# 491_Circuit_Schematic_to_MILL_mixed_4th.net
KiCad netlist of a schematic drawn in EAGLE
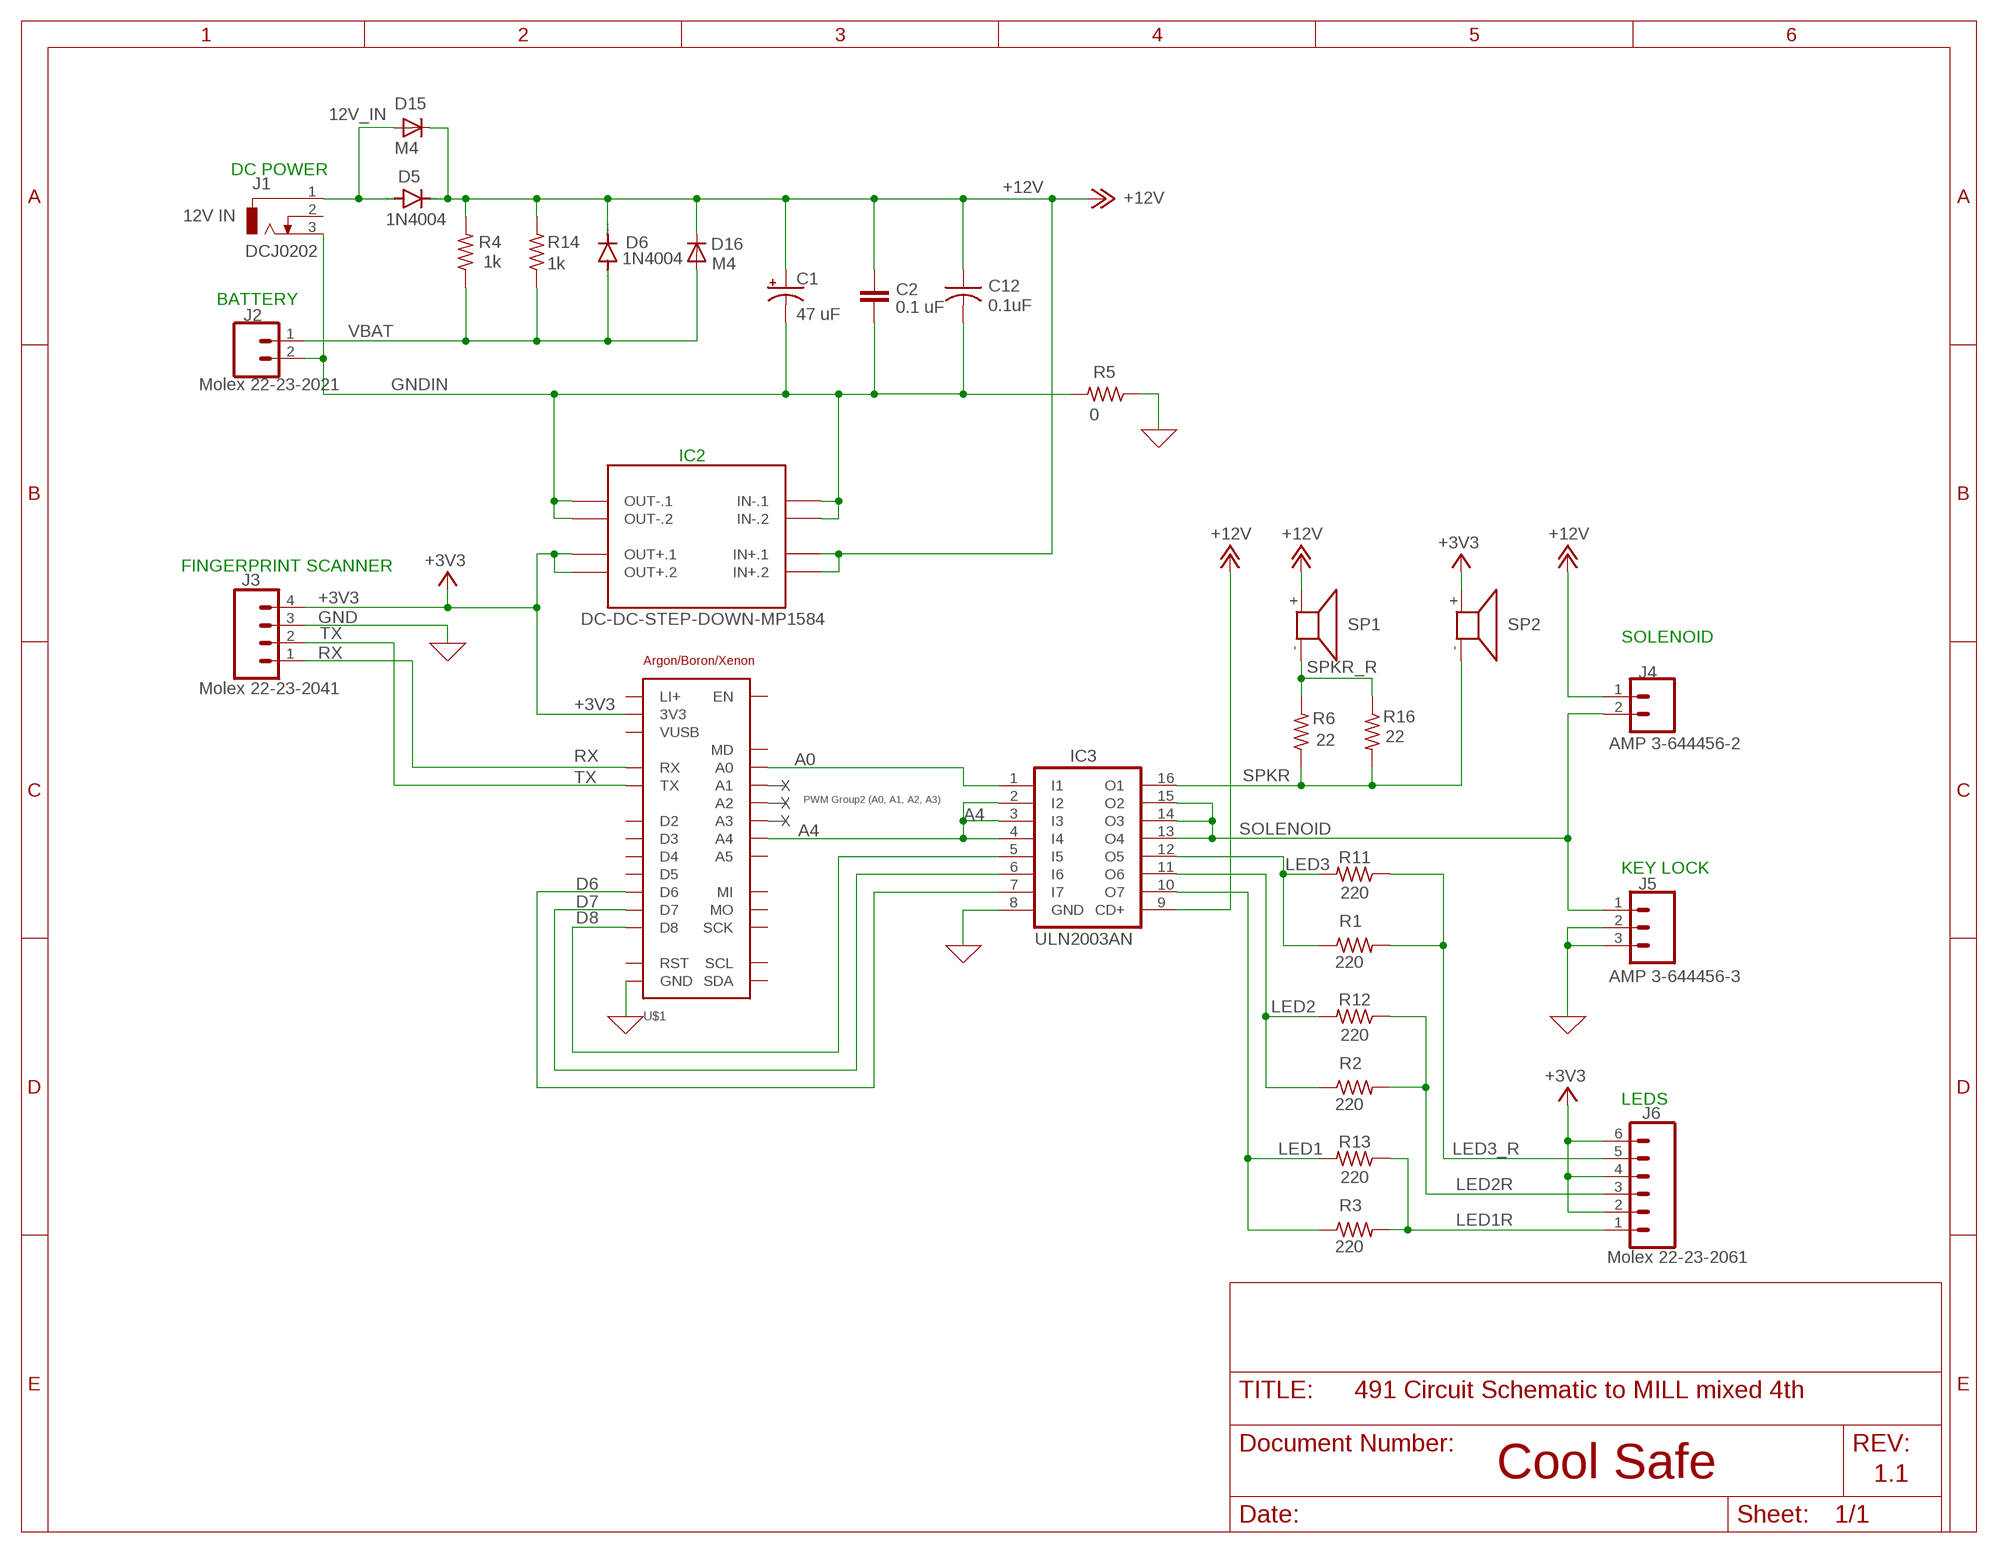
[diagram p0: schematic, sheet 1]

(export (version "E")
  (design (tool "Eeschema 10.0.6"))
  (components
    (comp (ref "C1")
      (value "47 uF")
      (footprint "eagle-import:E2,5-6")
      (libsource (lib "eagle-import") (part "CPOL-USE2.5-6"))
    )
    (comp (ref "C2")
      (value "0.1 uF")
      (footprint "eagle-import:C2.5-5")
      (libsource (lib "eagle-import") (part "C2.5/5"))
    )
    (comp (ref "C12")
      (value "0.1uF")
      (footprint "eagle-import:C1206")
      (libsource (lib "eagle-import") (part "C-USC1206"))
    )
    (comp (ref "D5")
      (value "1N4004")
      (footprint "eagle-import:DO41-10")
      (fields (field (name "POPULARITY") "82"))
      (libsource (lib "eagle-import") (part "1N4004"))
    )
    (comp (ref "D6")
      (value "1N4004")
      (footprint "eagle-import:DO41-10")
      (libsource (lib "eagle-import") (part "1N4004"))
    )
    (comp (ref "D15")
      (value "M4")
      (footprint "eagle-import:SMA-DO214AC")
      (libsource (lib "eagle-import") (part "GF1"))
    )
    (comp (ref "D16")
      (value "M4")
      (footprint "eagle-import:SMA-DO214AC")
      (libsource (lib "eagle-import") (part "GF1"))
    )
    (comp (ref "IC2")
      (value "DC-DC-STEP-DOWN-MP1584")
      (footprint "eagle-import:DC-DC-STEP-DOWN-MP1584")
      (libsource (lib "eagle-import") (part "DC-DC-STEP-DOWN-MP1584"))
    )
    (comp (ref "IC3")
      (value "ULN2003AN")
      (footprint "eagle-import:DIL16")
      (libsource (lib "eagle-import") (part "ULN2003AN"))
    )
    (comp (ref "J1")
      (value "DCJ0202")
      (footprint "eagle-import:DCJ0202")
      (libsource (lib "eagle-import") (part "DCJ0202"))
    )
    (comp (ref "J2")
      (value "Molex 22-23-2021")
      (footprint "eagle-import:MOLEX-1X2")
      (libsource (lib "eagle-import") (part "CONN_02POLAR"))
    )
    (comp (ref "J3")
      (value "Molex 22-23-2041")
      (footprint "eagle-import:MOLEX-1X4")
      (libsource (lib "eagle-import") (part "CONN_04POLAR"))
    )
    (comp (ref "J4")
      (value "AMP 3-644456-2")
      (footprint "eagle-import:1X02")
      (libsource (lib "eagle-import") (part "CONN_02"))
    )
    (comp (ref "J5")
      (value "AMP 3-644456-3")
      (footprint "eagle-import:1X03")
      (libsource (lib "eagle-import") (part "CONN_03"))
    )
    (comp (ref "J6")
      (value "Molex 22-23-2061")
      (footprint "eagle-import:MOLEX-1X6")
      (libsource (lib "eagle-import") (part "CONN_06POLAR"))
    )
    (comp (ref "R1")
      (value "220")
      (footprint "eagle-import:0207_10")
      (libsource (lib "eagle-import") (part "R-US_0207/10"))
    )
    (comp (ref "R2")
      (value "220")
      (footprint "eagle-import:0207_10")
      (libsource (lib "eagle-import") (part "R-US_0207/10"))
    )
    (comp (ref "R3")
      (value "220")
      (footprint "eagle-import:0207_10")
      (libsource (lib "eagle-import") (part "R-US_0207/10"))
    )
    (comp (ref "R4")
      (value "1k")
      (footprint "eagle-import:0207_10")
      (libsource (lib "eagle-import") (part "R-US_0207/10"))
    )
    (comp (ref "R5")
      (value "0")
      (footprint "eagle-import:0207_10")
      (libsource (lib "eagle-import") (part "R-US_0207/10"))
    )
    (comp (ref "R6")
      (value "22")
      (footprint "eagle-import:0204_7")
      (libsource (lib "eagle-import") (part "R-US_0204/7"))
    )
    (comp (ref "R11")
      (value "220")
      (footprint "eagle-import:M1206")
      (libsource (lib "eagle-import") (part "R-US_M1206"))
    )
    (comp (ref "R12")
      (value "220")
      (footprint "eagle-import:M1206")
      (libsource (lib "eagle-import") (part "R-US_M1206"))
    )
    (comp (ref "R13")
      (value "220")
      (footprint "eagle-import:M1206")
      (libsource (lib "eagle-import") (part "R-US_M1206"))
    )
    (comp (ref "R14")
      (value "1k")
      (footprint "eagle-import:M1206")
      (libsource (lib "eagle-import") (part "R-US_M1206"))
    )
    (comp (ref "R16")
      (value "22")
      (footprint "eagle-import:M1206")
      (libsource (lib "eagle-import") (part "R-US_M1206"))
    )
    (comp (ref "SP1")
      (value "KSS1201")
      (footprint "eagle-import:KSS1201")
      (libsource (lib "eagle-import") (part "KSS1201"))
    )
    (comp (ref "SP2")
      (value "KSS1201")
      (footprint "eagle-import:KSS1201")
      (fields
        (field (name "OC_FARNELL") "unknown")
        (field (name "OC_NEWARK") "unknown")
        (field (name "POPULARITY") "1")
      )
      (libsource (lib "eagle-import") (part "KSS1201"))
    )
    (comp (ref "U$1")
      (value "TEMPLATE_ARGON/BORON/XENONPTH")
      (footprint "eagle-import:NO_PADS")
      (libsource (lib "eagle-import") (part "TEMPLATE_ARGON/BORON/XENONPTH"))
    )
  )
  (nets
    (net (code "1") (name "+3V3") (class "Default")
      (node (ref "IC2") (pin "OUT+.1") (pinfunction "OUT+.1_OUT+.1") (pintype "bidirectional"))
      (node (ref "IC2") (pin "OUT+.2") (pinfunction "OUT+.2_OUT+.2") (pintype "bidirectional"))
      (node (ref "J3") (pin "4") (pinfunction "4_4") (pintype "passive"))
      (node (ref "J6") (pin "2") (pinfunction "2_2") (pintype "passive"))
      (node (ref "J6") (pin "4") (pinfunction "4_4") (pintype "passive"))
      (node (ref "J6") (pin "6") (pinfunction "6_6") (pintype "passive"))
      (node (ref "SP2") (pin "+") (pinfunction "1_+") (pintype "passive"))
      (node (ref "U$1") (pin "P$14") (pinfunction "3V3_P$14") (pintype "bidirectional"))
    )
    (net (code "2") (name "+12V") (class "Default")
      (node (ref "C1") (pin "+") (pinfunction "+_+") (pintype "passive"))
      (node (ref "C12") (pin "1") (pinfunction "1_1") (pintype "passive"))
      (node (ref "C2") (pin "1") (pinfunction "1_1") (pintype "passive"))
      (node (ref "D15") (pin "K") (pinfunction "C_K") (pintype "passive"))
      (node (ref "D16") (pin "K") (pinfunction "C_K") (pintype "passive"))
      (node (ref "D5") (pin "C") (pinfunction "C_C") (pintype "passive"))
      (node (ref "D6") (pin "C") (pinfunction "C_C") (pintype "passive"))
      (node (ref "IC2") (pin "IN+.1") (pinfunction "IN+.1_IN+.1") (pintype "bidirectional"))
      (node (ref "IC2") (pin "IN+.2") (pinfunction "IN+.2_IN+.2") (pintype "bidirectional"))
      (node (ref "IC3") (pin "9") (pinfunction "CD+_9") (pintype "passive"))
      (node (ref "J4") (pin "1") (pinfunction "1_1") (pintype "passive"))
      (node (ref "R14") (pin "2") (pinfunction "2_2") (pintype "passive"))
      (node (ref "R4") (pin "2") (pinfunction "2_2") (pintype "passive"))
      (node (ref "SP1") (pin "+") (pinfunction "1_+") (pintype "passive"))
    )
    (net (code "3") (name "/12V_IN") (class "Default")
      (node (ref "D15") (pin "A") (pinfunction "A_A") (pintype "passive"))
      (node (ref "D5") (pin "A") (pinfunction "A_A") (pintype "passive"))
      (node (ref "J1") (pin "1") (pinfunction "1_1") (pintype "passive"))
    )
    (net (code "4") (name "/A0") (class "Default")
      (node (ref "IC3") (pin "1") (pinfunction "I1_1") (pintype "input"))
      (node (ref "U$1") (pin "P$17") (pinfunction "A0_P$17") (pintype "bidirectional"))
    )
    (net (code "5") (name "/A4") (class "Default")
      (node (ref "IC3") (pin "2") (pinfunction "I2_2") (pintype "input"))
      (node (ref "IC3") (pin "3") (pinfunction "I3_3") (pintype "input"))
      (node (ref "IC3") (pin "4") (pinfunction "I4_4") (pintype "input"))
      (node (ref "U$1") (pin "P$21") (pinfunction "A4_P$21") (pintype "bidirectional"))
    )
    (net (code "6") (name "/D6") (class "Default")
      (node (ref "IC3") (pin "7") (pinfunction "I7_7") (pintype "input"))
      (node (ref "U$1") (pin "P$6") (pinfunction "D6_P$6") (pintype "bidirectional"))
    )
    (net (code "7") (name "/D7") (class "Default")
      (node (ref "IC3") (pin "6") (pinfunction "I6_6") (pintype "input"))
      (node (ref "U$1") (pin "P$5") (pinfunction "D7_P$5") (pintype "bidirectional"))
    )
    (net (code "8") (name "/D8") (class "Default")
      (node (ref "IC3") (pin "5") (pinfunction "I5_5") (pintype "input"))
      (node (ref "U$1") (pin "P$4") (pinfunction "D8_P$4") (pintype "bidirectional"))
    )
    (net (code "9") (name "/GNDIN") (class "Default")
      (node (ref "C1") (pin "-") (pinfunction "-_-") (pintype "passive"))
      (node (ref "C12") (pin "2") (pinfunction "2_2") (pintype "passive"))
      (node (ref "C2") (pin "2") (pinfunction "2_2") (pintype "passive"))
      (node (ref "IC2") (pin "IN-.1") (pinfunction "IN-.1_IN-.1") (pintype "bidirectional"))
      (node (ref "IC2") (pin "IN-.2") (pinfunction "IN-.2_IN-.2") (pintype "bidirectional"))
      (node (ref "IC2") (pin "OUT-.1") (pinfunction "OUT-.1_OUT-.1") (pintype "bidirectional"))
      (node (ref "IC2") (pin "OUT-.2") (pinfunction "OUT-.2_OUT-.2") (pintype "bidirectional"))
      (node (ref "J1") (pin "3") (pinfunction "3_3") (pintype "passive"))
      (node (ref "J2") (pin "2") (pinfunction "2_2") (pintype "passive"))
      (node (ref "R5") (pin "2") (pinfunction "2_2") (pintype "passive"))
    )
    (net (code "10") (name "/LED1") (class "Default")
      (node (ref "IC3") (pin "10") (pinfunction "O7_10") (pintype "open_collector"))
      (node (ref "R13") (pin "2") (pinfunction "2_2") (pintype "passive"))
      (node (ref "R3") (pin "1") (pinfunction "1_1") (pintype "passive"))
    )
    (net (code "11") (name "/LED1R") (class "Default")
      (node (ref "J6") (pin "1") (pinfunction "1_1") (pintype "passive"))
      (node (ref "R13") (pin "1") (pinfunction "1_1") (pintype "passive"))
      (node (ref "R3") (pin "2") (pinfunction "2_2") (pintype "passive"))
    )
    (net (code "12") (name "/LED2") (class "Default")
      (node (ref "IC3") (pin "11") (pinfunction "O6_11") (pintype "open_collector"))
      (node (ref "R12") (pin "2") (pinfunction "2_2") (pintype "passive"))
      (node (ref "R2") (pin "1") (pinfunction "1_1") (pintype "passive"))
    )
    (net (code "13") (name "/LED2R") (class "Default")
      (node (ref "J6") (pin "3") (pinfunction "3_3") (pintype "passive"))
      (node (ref "R12") (pin "1") (pinfunction "1_1") (pintype "passive"))
      (node (ref "R2") (pin "2") (pinfunction "2_2") (pintype "passive"))
    )
    (net (code "14") (name "/LED3") (class "Default")
      (node (ref "IC3") (pin "12") (pinfunction "O5_12") (pintype "open_collector"))
      (node (ref "R1") (pin "1") (pinfunction "1_1") (pintype "passive"))
      (node (ref "R11") (pin "2") (pinfunction "2_2") (pintype "passive"))
    )
    (net (code "15") (name "/LED3_R") (class "Default")
      (node (ref "J6") (pin "5") (pinfunction "5_5") (pintype "passive"))
      (node (ref "R1") (pin "2") (pinfunction "2_2") (pintype "passive"))
      (node (ref "R11") (pin "1") (pinfunction "1_1") (pintype "passive"))
    )
    (net (code "16") (name "/RX") (class "Default")
      (node (ref "J3") (pin "1") (pinfunction "1_1") (pintype "passive"))
      (node (ref "U$1") (pin "P$26") (pinfunction "RX_P$26") (pintype "bidirectional"))
    )
    (net (code "17") (name "/SOLENOID") (class "Default")
      (node (ref "IC3") (pin "13") (pinfunction "O4_13") (pintype "open_collector"))
      (node (ref "IC3") (pin "14") (pinfunction "O3_14") (pintype "open_collector"))
      (node (ref "IC3") (pin "15") (pinfunction "O2_15") (pintype "open_collector"))
      (node (ref "J4") (pin "2") (pinfunction "2_2") (pintype "passive"))
      (node (ref "J5") (pin "1") (pinfunction "1_1") (pintype "passive"))
    )
    (net (code "18") (name "/SPKR") (class "Default")
      (node (ref "IC3") (pin "16") (pinfunction "O1_16") (pintype "open_collector"))
      (node (ref "R16") (pin "2") (pinfunction "2_2") (pintype "passive"))
      (node (ref "R6") (pin "1") (pinfunction "1_1") (pintype "passive"))
      (node (ref "SP2") (pin "-") (pinfunction "2_-") (pintype "passive"))
    )
    (net (code "19") (name "/SPKR_R") (class "Default")
      (node (ref "R16") (pin "1") (pinfunction "1_1") (pintype "passive"))
      (node (ref "R6") (pin "2") (pinfunction "2_2") (pintype "passive"))
      (node (ref "SP1") (pin "-") (pinfunction "2_-") (pintype "passive"))
    )
    (net (code "20") (name "/TX") (class "Default")
      (node (ref "J3") (pin "2") (pinfunction "2_2") (pintype "passive"))
      (node (ref "U$1") (pin "P$27") (pinfunction "TX_P$27") (pintype "bidirectional"))
    )
    (net (code "21") (name "/VBAT") (class "Default")
      (node (ref "D16") (pin "A") (pinfunction "A_A") (pintype "passive"))
      (node (ref "D6") (pin "A") (pinfunction "A_A") (pintype "passive"))
      (node (ref "J2") (pin "1") (pinfunction "1_1") (pintype "passive"))
      (node (ref "R14") (pin "1") (pinfunction "1_1") (pintype "passive"))
      (node (ref "R4") (pin "1") (pinfunction "1_1") (pintype "passive"))
    )
    (net (code "22") (name "GND") (class "Default")
      (node (ref "IC3") (pin "8") (pinfunction "GND_8") (pintype "power_in"))
      (node (ref "J3") (pin "3") (pinfunction "3_3") (pintype "passive"))
      (node (ref "J5") (pin "2") (pinfunction "2_2") (pintype "passive"))
      (node (ref "J5") (pin "3") (pinfunction "3_3") (pintype "passive"))
      (node (ref "R5") (pin "1") (pinfunction "1_1") (pintype "passive"))
      (node (ref "U$1") (pin "P$16") (pinfunction "GND_P$16") (pintype "bidirectional"))
    )
    (net (code "23") (name "unconnected-(J1-Pad2)") (class "Default")
      (node (ref "J1") (pin "2") (pinfunction "2_2") (pintype "passive"))
    )
    (net (code "24") (name "unconnected-(U$1-A1-PadP$18)") (class "Default")
      (node (ref "U$1") (pin "P$18") (pinfunction "A1_P$18") (pintype "bidirectional"))
    )
    (net (code "25") (name "unconnected-(U$1-A2-PadP$19)") (class "Default")
      (node (ref "U$1") (pin "P$19") (pinfunction "A2_P$19") (pintype "bidirectional"))
    )
    (net (code "26") (name "unconnected-(U$1-A3-PadP$20)") (class "Default")
      (node (ref "U$1") (pin "P$20") (pinfunction "A3_P$20") (pintype "bidirectional"))
    )
    (net (code "27") (name "unconnected-(U$1-A5-PadP$22)") (class "Default")
      (node (ref "U$1") (pin "P$22") (pinfunction "A5_P$22") (pintype "bidirectional"))
    )
    (net (code "28") (name "unconnected-(U$1-D2-PadP$10)") (class "Default")
      (node (ref "U$1") (pin "P$10") (pinfunction "D2_P$10") (pintype "bidirectional"))
    )
    (net (code "29") (name "unconnected-(U$1-D3-PadP$9)") (class "Default")
      (node (ref "U$1") (pin "P$9") (pinfunction "D3_P$9") (pintype "bidirectional"))
    )
    (net (code "30") (name "unconnected-(U$1-D4-PadP$8)") (class "Default")
      (node (ref "U$1") (pin "P$8") (pinfunction "D4_P$8") (pintype "bidirectional"))
    )
    (net (code "31") (name "unconnected-(U$1-D5-PadP$7)") (class "Default")
      (node (ref "U$1") (pin "P$7") (pinfunction "D5_P$7") (pintype "bidirectional"))
    )
    (net (code "32") (name "unconnected-(U$1-EN-PadP$2)") (class "Default")
      (node (ref "U$1") (pin "P$2") (pinfunction "EN_P$2") (pintype "bidirectional"))
    )
    (net (code "33") (name "unconnected-(U$1-LI+-PadP$1)") (class "Default")
      (node (ref "U$1") (pin "P$1") (pinfunction "LI+_P$1") (pintype "bidirectional"))
    )
    (net (code "34") (name "unconnected-(U$1-MD-PadP$15)") (class "Default")
      (node (ref "U$1") (pin "P$15") (pinfunction "MD_P$15") (pintype "bidirectional"))
    )
    (net (code "35") (name "unconnected-(U$1-MI-PadP$25)") (class "Default")
      (node (ref "U$1") (pin "P$25") (pinfunction "MI_P$25") (pintype "bidirectional"))
    )
    (net (code "36") (name "unconnected-(U$1-MO-PadP$24)") (class "Default")
      (node (ref "U$1") (pin "P$24") (pinfunction "MO_P$24") (pintype "bidirectional"))
    )
    (net (code "37") (name "unconnected-(U$1-RST-PadP$13)") (class "Default")
      (node (ref "U$1") (pin "P$13") (pinfunction "RST_P$13") (pintype "bidirectional"))
    )
    (net (code "38") (name "unconnected-(U$1-SCK-PadP$23)") (class "Default")
      (node (ref "U$1") (pin "P$23") (pinfunction "SCK_P$23") (pintype "bidirectional"))
    )
    (net (code "39") (name "unconnected-(U$1-SCL-PadP$11)") (class "Default")
      (node (ref "U$1") (pin "P$11") (pinfunction "SCL_P$11") (pintype "bidirectional"))
    )
    (net (code "40") (name "unconnected-(U$1-SDA-PadP$12)") (class "Default")
      (node (ref "U$1") (pin "P$12") (pinfunction "SDA_P$12") (pintype "bidirectional"))
    )
    (net (code "41") (name "unconnected-(U$1-VUSB-PadP$3)") (class "Default")
      (node (ref "U$1") (pin "P$3") (pinfunction "VUSB_P$3") (pintype "bidirectional"))
    )
  )
)
